# MCU.net
KiCad netlist of a schematic drawn in Altium Designer
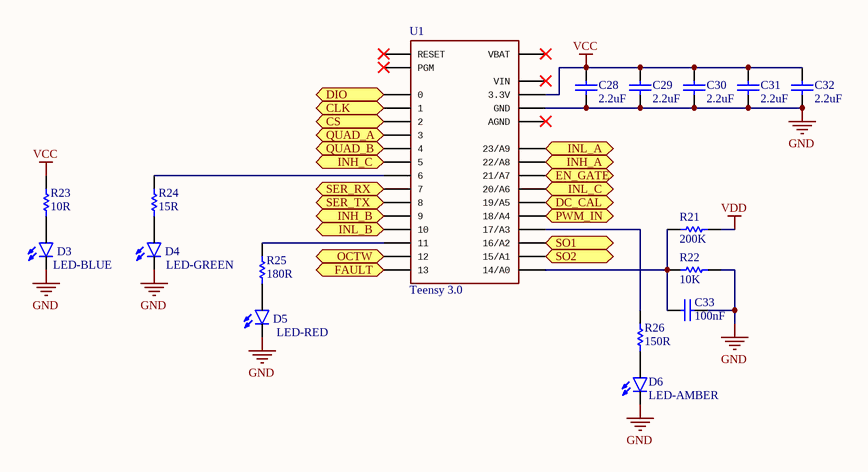
[diagram p0: MCU.SchDoc]

(export (version "E")
  (design (tool "Eeschema 10.0.6"))
  (components
    (comp (ref "C28")
      (value "2.2uF")
      (footprint "CAPC0603(1608)55_N")
      (description "CAP 2.2uF 16V Â±10% 0603 (1608 Metric) Thickness 0.55mm SMD")
      (fields (field (name "TOLERANCE") "Â±10%"))
      (libsource (lib "Altium Content Vault") (part "CMP-1035-02762-1"))
    )
    (comp (ref "C29")
      (value "2.2uF")
      (footprint "CAPC0603(1608)55_N")
      (description "CAP 2.2uF 16V Â±10% 0603 (1608 Metric) Thickness 0.55mm SMD")
      (fields (field (name "TOLERANCE") "Â±10%"))
      (libsource (lib "Altium Content Vault") (part "CMP-1035-02762-1"))
    )
    (comp (ref "C30")
      (value "2.2uF")
      (footprint "CAPC0603(1608)55_N")
      (description "CAP 2.2uF 16V Â±10% 0603 (1608 Metric) Thickness 0.55mm SMD")
      (fields (field (name "TOLERANCE") "Â±10%"))
      (libsource (lib "Altium Content Vault") (part "CMP-1035-02762-1"))
    )
    (comp (ref "C31")
      (value "2.2uF")
      (footprint "CAPC0603(1608)55_N")
      (description "CAP 2.2uF 16V Â±10% 0603 (1608 Metric) Thickness 0.55mm SMD")
      (fields (field (name "TOLERANCE") "Â±10%"))
      (libsource (lib "Altium Content Vault") (part "CMP-1035-02762-1"))
    )
    (comp (ref "C32")
      (value "2.2uF")
      (footprint "CAPC0603(1608)55_N")
      (description "CAP 2.2uF 16V Â±10% 0603 (1608 Metric) Thickness 0.55mm SMD")
      (fields (field (name "TOLERANCE") "Â±10%"))
      (libsource (lib "Altium Content Vault") (part "CMP-1035-02762-1"))
    )
    (comp (ref "C33")
      (value "100nF")
      (footprint "CAPC0603(1608)100_L")
      (description "CAP 100nF 50V Â±5% 0603 (1608 Metric) Thickness 1mm SMD")
      (fields (field (name "TOLERANCE") "Â±5%"))
      (libsource (lib "Altium Content Vault") (part "CAP"))
    )
    (comp (ref "D3")
      (value "LED-BLUE")
      (footprint "LED-1206")
      (libsource (lib "Components") (part "LED-BLUE1206"))
    )
    (comp (ref "D4")
      (value "LED-GREEN")
      (footprint "LED-1206")
      (libsource (lib "Components") (part "LED-GREEN1206"))
    )
    (comp (ref "D5")
      (value "LED-RED")
      (footprint "LED-1206")
      (libsource (lib "Components") (part "LED-RED1206"))
    )
    (comp (ref "D6")
      (value "LED-AMBER")
      (footprint "LED-1206")
      (libsource (lib "Components") (part "LED-AMBER1206"))
    )
    (comp (ref "R21")
      (value "200K")
      (footprint "RESC0603(1608)_L")
      (description "200K 0.1W 5% 0603 (1608 Metric)  SMD")
      (fields (field (name "POWER") "0.1 W") (field (name "TOLERANCE") "5 %"))
      (libsource (lib "Altium Content Vault") (part "RES"))
    )
    (comp (ref "R22")
      (value "10K")
      (footprint "RESC0603(1608)_M")
      (description "10K 0.1W 5% 0603 (1608 Metric)  SMD")
      (fields (field (name "TOLERANCE") "5 %") (field (name "POWER") "0.1 W"))
      (libsource (lib "Altium Content Vault") (part "RES"))
    )
    (comp (ref "R23")
      (value "10R")
      (footprint "RESC0603(1608)_M")
      (description "10R 0.1W 5% 0603 (1608 Metric)  SMD")
      (fields (field (name "TOLERANCE") "5 %") (field (name "POWER") "0.1 W"))
      (libsource (lib "Altium Content Vault") (part "RES"))
    )
    (comp (ref "R24")
      (value "15R")
      (footprint "RESC0603(1608)_M")
      (description "15R 0.1W 5% 0603 (1608 Metric)  SMD")
      (fields (field (name "TOLERANCE") "5 %") (field (name "POWER") "0.1 W"))
      (libsource (lib "Altium Content Vault") (part "RES"))
    )
    (comp (ref "R25")
      (value "180R")
      (footprint "RESC0603(1608)_M")
      (description "180R 0.1W 5% 0603 (1608 Metric)  SMD")
      (fields (field (name "POWER") "0.1 W") (field (name "TOLERANCE") "5 %"))
      (libsource (lib "Altium Content Vault") (part "RES"))
    )
    (comp (ref "R26")
      (value "150R")
      (footprint "RESC0603(1608)_M")
      (description "150R 0.1W 5% 0603 (1608 Metric)  SMD")
      (fields (field (name "POWER") "0.1 W") (field (name "TOLERANCE") "5 %"))
      (libsource (lib "Altium Content Vault") (part "RES"))
    )
    (comp (ref "U1")
      (value "Teensy 3.0")
      (footprint "TEENSY_3.0_BASIC")
      (libsource (lib "Teensy3.0") (part "TEENSY_3.0_BASIC"))
    )
  )
  (nets
    (net (code "1") (name "/CLK") (class "Default")
      (node (ref "U1") (pin "1") (pinfunction "1_1") (pintype "passive"))
    )
    (net (code "2") (name "/CS") (class "Default")
      (node (ref "U1") (pin "2") (pinfunction "2_2") (pintype "passive"))
    )
    (net (code "3") (name "/DC_CAL") (class "Default")
      (node (ref "U1") (pin "19/A5") (pinfunction "19/A5_19/A5") (pintype "passive"))
    )
    (net (code "4") (name "/DIO") (class "Default")
      (node (ref "U1") (pin "0") (pinfunction "0_0") (pintype "passive"))
    )
    (net (code "5") (name "/EN_GATE") (class "Default")
      (node (ref "U1") (pin "21/A7") (pinfunction "21/A7_21/A7") (pintype "passive"))
    )
    (net (code "6") (name "/FAULT") (class "Default")
      (node (ref "U1") (pin "13") (pinfunction "13_13") (pintype "passive"))
    )
    (net (code "7") (name "/INH_A") (class "Default")
      (node (ref "U1") (pin "22/A8") (pinfunction "22/A8_22/A8") (pintype "passive"))
    )
    (net (code "8") (name "/INH_B") (class "Default")
      (node (ref "U1") (pin "9") (pinfunction "9_9") (pintype "passive"))
    )
    (net (code "9") (name "/INH_C") (class "Default")
      (node (ref "U1") (pin "5") (pinfunction "5_5") (pintype "passive"))
    )
    (net (code "10") (name "/INL_A") (class "Default")
      (node (ref "U1") (pin "23/A9") (pinfunction "23/A9_23/A9") (pintype "passive"))
    )
    (net (code "11") (name "/INL_B") (class "Default")
      (node (ref "U1") (pin "10") (pinfunction "10_10") (pintype "passive"))
    )
    (net (code "12") (name "/INL_C") (class "Default")
      (node (ref "U1") (pin "20/A6") (pinfunction "20/A6_20/A6") (pintype "passive"))
    )
    (net (code "13") (name "/OCTW") (class "Default")
      (node (ref "U1") (pin "12") (pinfunction "12_12") (pintype "passive"))
    )
    (net (code "14") (name "/PWM_IN") (class "Default")
      (node (ref "U1") (pin "18/A4") (pinfunction "18/A4_18/A4") (pintype "passive"))
    )
    (net (code "15") (name "/QUAD_A") (class "Default")
      (node (ref "U1") (pin "3") (pinfunction "3_3") (pintype "passive"))
    )
    (net (code "16") (name "/QUAD_B") (class "Default")
      (node (ref "U1") (pin "4") (pinfunction "4_4") (pintype "passive"))
    )
    (net (code "17") (name "/SER_RX") (class "Default")
      (node (ref "U1") (pin "7") (pinfunction "7_7") (pintype "passive"))
    )
    (net (code "18") (name "/SER_TX") (class "Default")
      (node (ref "U1") (pin "8") (pinfunction "8_8") (pintype "passive"))
    )
    (net (code "19") (name "/SO1") (class "Default")
      (node (ref "U1") (pin "16/A2") (pinfunction "16/A2_16/A2") (pintype "passive"))
    )
    (net (code "20") (name "/SO2") (class "Default")
      (node (ref "U1") (pin "15/A1") (pinfunction "15/A1_15/A1") (pintype "passive"))
    )
    (net (code "21") (name "GND") (class "Default")
      (node (ref "C28") (pin "1") (pinfunction "1_1") (pintype "passive"))
      (node (ref "C29") (pin "1") (pinfunction "1_1") (pintype "passive"))
      (node (ref "C30") (pin "1") (pinfunction "1_1") (pintype "passive"))
      (node (ref "C31") (pin "1") (pinfunction "1_1") (pintype "passive"))
      (node (ref "C32") (pin "1") (pinfunction "1_1") (pintype "passive"))
      (node (ref "C33") (pin "2") (pinfunction "2_2") (pintype "passive"))
      (node (ref "D3") (pin "C") (pinfunction "C_C") (pintype "passive"))
      (node (ref "D4") (pin "C") (pinfunction "C_C") (pintype "passive"))
      (node (ref "D5") (pin "C") (pinfunction "C_C") (pintype "passive"))
      (node (ref "D6") (pin "C") (pinfunction "C_C") (pintype "passive"))
      (node (ref "R22") (pin "2") (pinfunction "2_2") (pintype "passive"))
      (node (ref "U1") (pin "GND_GND1") (pinfunction "GND_GND_GND1") (pintype "power_in"))
    )
    (net (code "22") (name "Net-(C33-Pad1)") (class "Default")
      (node (ref "C33") (pin "1") (pinfunction "1_1") (pintype "passive"))
      (node (ref "R21") (pin "1") (pinfunction "1_1") (pintype "passive"))
      (node (ref "R22") (pin "1") (pinfunction "1_1") (pintype "passive"))
      (node (ref "U1") (pin "14/A0") (pinfunction "14/A0_14/A0") (pintype "passive"))
    )
    (net (code "23") (name "Net-(D3-PadA)") (class "Default")
      (node (ref "D3") (pin "A") (pinfunction "A_A") (pintype "passive"))
      (node (ref "R23") (pin "1") (pinfunction "1_1") (pintype "passive"))
    )
    (net (code "24") (name "Net-(D4-PadA)") (class "Default")
      (node (ref "D4") (pin "A") (pinfunction "A_A") (pintype "passive"))
      (node (ref "R24") (pin "1") (pinfunction "1_1") (pintype "passive"))
    )
    (net (code "25") (name "Net-(D5-PadA)") (class "Default")
      (node (ref "D5") (pin "A") (pinfunction "A_A") (pintype "passive"))
      (node (ref "R25") (pin "1") (pinfunction "1_1") (pintype "passive"))
    )
    (net (code "26") (name "Net-(D6-PadA)") (class "Default")
      (node (ref "D6") (pin "A") (pinfunction "A_A") (pintype "passive"))
      (node (ref "R26") (pin "1") (pinfunction "1_1") (pintype "passive"))
    )
    (net (code "27") (name "Net-(R24-Pad2)") (class "Default")
      (node (ref "R24") (pin "2") (pinfunction "2_2") (pintype "passive"))
      (node (ref "U1") (pin "6") (pinfunction "6_6") (pintype "passive"))
    )
    (net (code "28") (name "Net-(R25-Pad2)") (class "Default")
      (node (ref "R25") (pin "2") (pinfunction "2_2") (pintype "passive"))
      (node (ref "U1") (pin "11") (pinfunction "11_11") (pintype "passive"))
    )
    (net (code "29") (name "Net-(R26-Pad2)") (class "Default")
      (node (ref "R26") (pin "2") (pinfunction "2_2") (pintype "passive"))
      (node (ref "U1") (pin "17/A3") (pinfunction "17/A3_17/A3") (pintype "passive"))
    )
    (net (code "30") (name "VCC") (class "Default")
      (node (ref "C28") (pin "2") (pinfunction "2_2") (pintype "passive"))
      (node (ref "C29") (pin "2") (pinfunction "2_2") (pintype "passive"))
      (node (ref "C30") (pin "2") (pinfunction "2_2") (pintype "passive"))
      (node (ref "C31") (pin "2") (pinfunction "2_2") (pintype "passive"))
      (node (ref "C32") (pin "2") (pinfunction "2_2") (pintype "passive"))
      (node (ref "R23") (pin "2") (pinfunction "2_2") (pintype "passive"))
      (node (ref "U1") (pin "3.3V_3.3V1") (pinfunction "3.3V_3.3V_3.3V1") (pintype "power_in"))
    )
    (net (code "31") (name "VDD") (class "Default")
      (node (ref "R21") (pin "2") (pinfunction "2_2") (pintype "passive"))
    )
    (net (code "32") (name "unconnected-(U1-PadAGND)") (class "Default")
      (node (ref "U1") (pin "AGND") (pinfunction "AGND_AGND") (pintype "power_in+no_connect"))
    )
    (net (code "33") (name "unconnected-(U1-PadPGM)") (class "Default")
      (node (ref "U1") (pin "PGM") (pinfunction "PGM_PGM") (pintype "passive+no_connect"))
    )
    (net (code "34") (name "unconnected-(U1-PadRESET)") (class "Default")
      (node (ref "U1") (pin "RESET") (pinfunction "RESET_RESET") (pintype "passive+no_connect"))
    )
    (net (code "35") (name "unconnected-(U1-PadVBAT)") (class "Default")
      (node (ref "U1") (pin "VBAT") (pinfunction "VBAT_VBAT") (pintype "power_in+no_connect"))
    )
    (net (code "36") (name "unconnected-(U1-PadVIN)") (class "Default")
      (node (ref "U1") (pin "VIN") (pinfunction "VIN_VIN") (pintype "power_in+no_connect"))
    )
  )
)
